# Output_Driver.net
KiCad netlist of a schematic drawn in Altium Designer
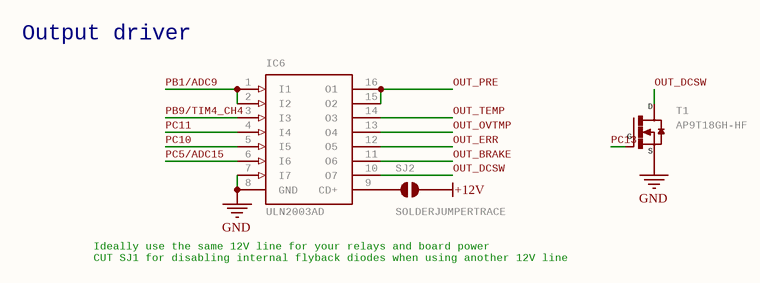
[diagram p0: Output Driver.SchDoc]

(export (version "E")
  (design (tool "Eeschema 10.0.6"))
  (components
    (comp (ref "IC6")
      (value "ULN2003AD")
      (footprint "SO16")
      (description "DRIVER ARRAY")
      (fields (field (name "LIBRARYNAME") "uln-udn"))
      (libsource (lib "Gate Driver Board") (part "ULN2003AD"))
    )
    (comp (ref "SJ2")
      (value "SOLDERJUMPERTRACE")
      (footprint "SJ_2S-TRACE")
      (libsource (lib "SparkFun-Passives") (part "SOLDERJUMPERTRACE"))
    )
    (comp (ref "T1")
      (value "AP9T18GH-HF")
      (footprint "D-PAK_TO252AA")
      (fields (field (name "D") "D") (field (name "S") "S") (field (name "G") "G"))
      (libsource (lib "Gate Driver Board") (part "AP9T18GH-HF"))
    )
  )
  (nets
    (net (code "1") (name "+12V") (class "Default")
      (node (ref "SJ2") (pin "2") (pinfunction "2_2") (pintype "passive"))
    )
    (net (code "2") (name "/OUT_BRAKE") (class "Default")
      (node (ref "IC6") (pin "11") (pinfunction "O6_11") (pintype "open_collector"))
    )
    (net (code "3") (name "/OUT_DCSW") (class "Default")
      (node (ref "IC6") (pin "10") (pinfunction "O7_10") (pintype "open_collector"))
      (node (ref "T1") (pin "4") (pinfunction "D_4") (pintype "passive"))
    )
    (net (code "4") (name "/OUT_ERR") (class "Default")
      (node (ref "IC6") (pin "12") (pinfunction "O5_12") (pintype "open_collector"))
    )
    (net (code "5") (name "/OUT_OVTMP") (class "Default")
      (node (ref "IC6") (pin "13") (pinfunction "O4_13") (pintype "open_collector"))
    )
    (net (code "6") (name "/OUT_PRE") (class "Default")
      (node (ref "IC6") (pin "15") (pinfunction "O2_15") (pintype "open_collector"))
      (node (ref "IC6") (pin "16") (pinfunction "O1_16") (pintype "open_collector"))
    )
    (net (code "7") (name "/OUT_TEMP") (class "Default")
      (node (ref "IC6") (pin "14") (pinfunction "O3_14") (pintype "open_collector"))
    )
    (net (code "8") (name "/PB1{slash}ADC9") (class "Default")
      (node (ref "IC6") (pin "1") (pinfunction "I1_1") (pintype "input"))
      (node (ref "IC6") (pin "2") (pinfunction "I2_2") (pintype "input"))
    )
    (net (code "9") (name "/PB9{slash}TIM4_CH4") (class "Default")
      (node (ref "IC6") (pin "3") (pinfunction "I3_3") (pintype "input"))
    )
    (net (code "10") (name "/PC5{slash}ADC15") (class "Default")
      (node (ref "IC6") (pin "6") (pinfunction "I6_6") (pintype "input"))
    )
    (net (code "11") (name "/PC10") (class "Default")
      (node (ref "IC6") (pin "5") (pinfunction "I5_5") (pintype "input"))
    )
    (net (code "12") (name "/PC11") (class "Default")
      (node (ref "IC6") (pin "4") (pinfunction "I4_4") (pintype "input"))
    )
    (net (code "13") (name "/PC13") (class "Default")
      (node (ref "T1") (pin "1") (pinfunction "G_1") (pintype "passive"))
    )
    (net (code "14") (name "GND") (class "Default")
      (node (ref "IC6") (pin "7") (pinfunction "I7_7") (pintype "input"))
      (node (ref "IC6") (pin "8") (pinfunction "GND_8") (pintype "power_in"))
      (node (ref "T1") (pin "3") (pinfunction "S_3") (pintype "passive"))
    )
    (net (code "15") (name "Net-(IC6-CD+)") (class "Default")
      (node (ref "IC6") (pin "9") (pinfunction "CD+_9") (pintype "passive"))
      (node (ref "SJ2") (pin "1") (pinfunction "1_1") (pintype "passive"))
    )
  )
)
